# FPGA_34.net
KiCad netlist of a schematic drawn in Altium Designer
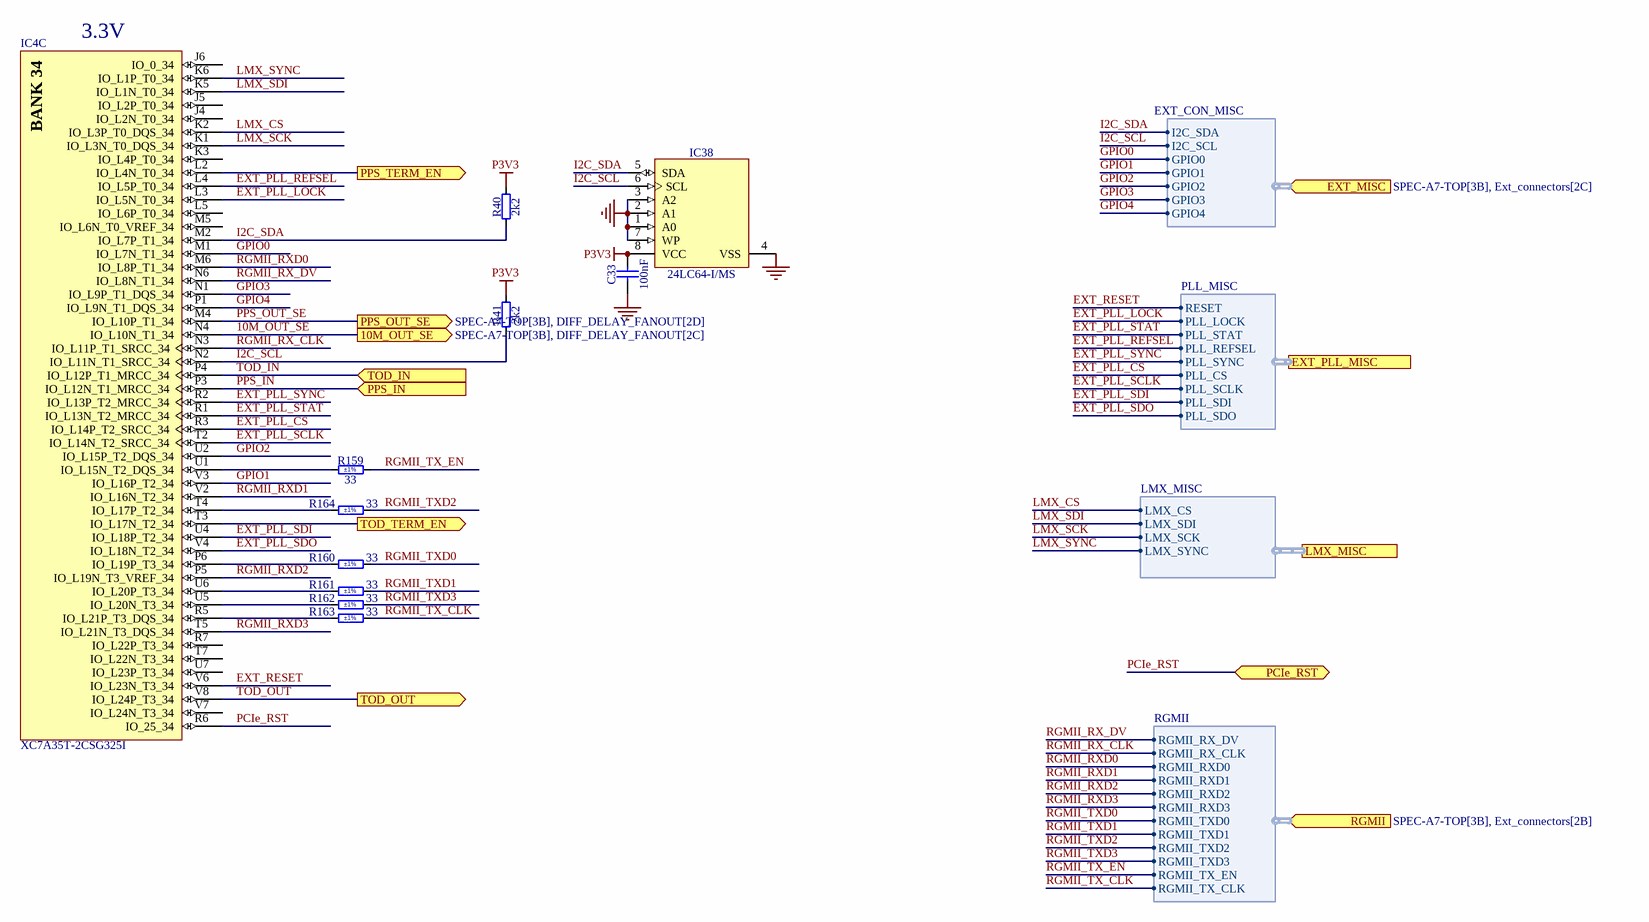
[diagram p0: FPGA_34.SchDoc]

(export (version "E")
  (design (tool "Eeschema 10.0.6"))
  (components
    (comp (ref "C33")
      (value "100nF")
      (footprint "CAPC0603X33N")
      (description "Non-polarised capacitor")
      (fields
        (field (name "PART NUMBER") "CC0201_100NF_6.3V_10%_X5R")
        (field (name "VOLTAGE") "6.3V")
        (field (name "AUTHOR") "CERN DEM JLC")
      )
      (libsource (lib "Capacitors") (part "Capacitor - non polarized"))
    )
    (comp (ref "IC4")
      (value "XC7A35T-2CSG325I")
      (footprint "CSG325")
      (description "Artix-7 FPGA, 150 User I/Os, 4 GTP, 324-Ball BGA, Speed Grade 2, Industrial Grade, Pb-Free")
      (fields (field (name "MANUFACTURER") "Xilinx"))
      (libsource (lib "Altium Content Vault") (part "XLNX-XC7A35T-CSG325"))
    )
    (comp (ref "IC38")
      (value "24LC64-I/MS")
      (footprint "SOP65P490X110-8N")
      (description "64K I2C Serial EEPROM")
      (fields (field (name "MANUFACTURER") "MICROCHIP TECHNOLOGY") (field (name "AUTHOR") "CERN DEM JLC"))
      (libsource (lib "ICs And Semiconductors") (part "24LC64-I/MS"))
    )
    (comp (ref "R40")
      (value "2k2")
      (footprint "RESC1005X40N")
      (description "Resistor - 1%")
      (fields
        (field (name "PART NUMBER") "R0402_2K2_1%_0.0625W_100PPM")
        (field (name "POWER") "0.0625W")
        (field (name "AUTHOR") "CERN DEM JLC")
      )
      (libsource (lib "Resistors") (part "Resistor - 1%"))
    )
    (comp (ref "R41")
      (value "2k2")
      (footprint "RESC1005X40N")
      (description "Resistor - 1%")
      (fields
        (field (name "PART NUMBER") "R0402_2K2_1%_0.0625W_100PPM")
        (field (name "POWER") "0.0625W")
        (field (name "AUTHOR") "CERN DEM JLC")
      )
      (libsource (lib "Resistors") (part "Resistor - 1%"))
    )
    (comp (ref "R159")
      (value "33")
      (footprint "RESC1005X40N")
      (description "Resistor - 1%")
      (fields
        (field (name "TOLERANCE") "±1%")
        (field (name "PART NUMBER") "R0402_33R_1%_0.0625W_100PPM")
        (field (name "POWER") "0.0625W")
        (field (name "AUTHOR") "CERN DEM JLC")
      )
      (libsource (lib "Resistors") (part "Resistor - 1%"))
    )
    (comp (ref "R160")
      (value "33")
      (footprint "RESC1005X40N")
      (description "Resistor - 1%")
      (fields
        (field (name "TOLERANCE") "±1%")
        (field (name "PART NUMBER") "R0402_33R_1%_0.0625W_100PPM")
        (field (name "POWER") "0.0625W")
        (field (name "AUTHOR") "CERN DEM JLC")
      )
      (libsource (lib "Resistors") (part "Resistor - 1%"))
    )
    (comp (ref "R161")
      (value "33")
      (footprint "RESC1005X40N")
      (description "Resistor - 1%")
      (fields
        (field (name "TOLERANCE") "±1%")
        (field (name "PART NUMBER") "R0402_33R_1%_0.0625W_100PPM")
        (field (name "POWER") "0.0625W")
        (field (name "AUTHOR") "CERN DEM JLC")
      )
      (libsource (lib "Resistors") (part "Resistor - 1%"))
    )
    (comp (ref "R162")
      (value "33")
      (footprint "RESC1005X40N")
      (description "Resistor - 1%")
      (fields
        (field (name "TOLERANCE") "±1%")
        (field (name "PART NUMBER") "R0402_33R_1%_0.0625W_100PPM")
        (field (name "POWER") "0.0625W")
        (field (name "AUTHOR") "CERN DEM JLC")
      )
      (libsource (lib "Resistors") (part "Resistor - 1%"))
    )
    (comp (ref "R163")
      (value "33")
      (footprint "RESC1005X40N")
      (description "Resistor - 1%")
      (fields
        (field (name "TOLERANCE") "±1%")
        (field (name "PART NUMBER") "R0402_33R_1%_0.0625W_100PPM")
        (field (name "POWER") "0.0625W")
        (field (name "AUTHOR") "CERN DEM JLC")
      )
      (libsource (lib "Resistors") (part "Resistor - 1%"))
    )
    (comp (ref "R164")
      (value "33")
      (footprint "RESC1005X40N")
      (description "Resistor - 1%")
      (fields
        (field (name "TOLERANCE") "±1%")
        (field (name "PART NUMBER") "R0402_33R_1%_0.0625W_100PPM")
        (field (name "POWER") "0.0625W")
        (field (name "AUTHOR") "CERN DEM JLC")
      )
      (libsource (lib "Resistors") (part "Resistor - 1%"))
    )
  )
  (nets
    (net (code "5") (name "/10M_OUT_SE") (class "Default")
      (node (ref "IC4") (pin "N4") (pinfunction "IO_L10N_T1_34_N4") (pintype "bidirectional"))
    )
    (net (code "6") (name "/EXT_PLL_CS") (class "Default")
      (node (ref "IC4") (pin "R3") (pinfunction "IO_L14P_T2_SRCC_34_R3") (pintype "bidirectional"))
    )
    (net (code "7") (name "/EXT_PLL_LOCK") (class "Default")
      (node (ref "IC4") (pin "L3") (pinfunction "IO_L5N_T0_34_L3") (pintype "bidirectional"))
    )
    (net (code "8") (name "/EXT_PLL_REFSEL") (class "Default")
      (node (ref "IC4") (pin "L4") (pinfunction "IO_L5P_T0_34_L4") (pintype "bidirectional"))
    )
    (net (code "9") (name "/EXT_PLL_SCLK") (class "Default")
      (node (ref "IC4") (pin "T2") (pinfunction "IO_L14N_T2_SRCC_34_T2") (pintype "bidirectional"))
    )
    (net (code "10") (name "/EXT_PLL_SDI") (class "Default")
      (node (ref "IC4") (pin "U4") (pinfunction "IO_L18P_T2_34_U4") (pintype "bidirectional"))
    )
    (net (code "11") (name "/EXT_PLL_SDO") (class "Default")
      (node (ref "IC4") (pin "V4") (pinfunction "IO_L18N_T2_34_V4") (pintype "bidirectional"))
    )
    (net (code "12") (name "/EXT_PLL_STAT") (class "Default")
      (node (ref "IC4") (pin "R1") (pinfunction "IO_L13N_T2_MRCC_34_R1") (pintype "bidirectional"))
    )
    (net (code "13") (name "/EXT_PLL_SYNC") (class "Default")
      (node (ref "IC4") (pin "R2") (pinfunction "IO_L13P_T2_MRCC_34_R2") (pintype "bidirectional"))
    )
    (net (code "14") (name "/EXT_RESET") (class "Default")
      (node (ref "IC4") (pin "V6") (pinfunction "IO_L23N_T3_34_V6") (pintype "bidirectional"))
    )
    (net (code "15") (name "/GPIO0") (class "Default")
      (node (ref "IC4") (pin "M1") (pinfunction "IO_L7N_T1_34_M1") (pintype "bidirectional"))
    )
    (net (code "16") (name "/GPIO1") (class "Default")
      (node (ref "IC4") (pin "V3") (pinfunction "IO_L16P_T2_34_V3") (pintype "bidirectional"))
    )
    (net (code "17") (name "/GPIO2") (class "Default")
      (node (ref "IC4") (pin "U2") (pinfunction "IO_L15P_T2_DQS_34_U2") (pintype "bidirectional"))
    )
    (net (code "18") (name "/GPIO3") (class "Default")
      (node (ref "IC4") (pin "N1") (pinfunction "IO_L9P_T1_DQS_34_N1") (pintype "bidirectional"))
    )
    (net (code "19") (name "/GPIO4") (class "Default")
      (node (ref "IC4") (pin "P1") (pinfunction "IO_L9N_T1_DQS_34_P1") (pintype "bidirectional"))
    )
    (net (code "20") (name "/I2C_SCL") (class "Default")
      (node (ref "IC38") (pin "6") (pinfunction "SCL_6") (pintype "input"))
      (node (ref "IC4") (pin "N2") (pinfunction "IO_L11N_T1_SRCC_34_N2") (pintype "bidirectional"))
      (node (ref "R41") (pin "1") (pinfunction "1_1") (pintype "passive"))
    )
    (net (code "21") (name "/I2C_SDA") (class "Default")
      (node (ref "IC38") (pin "5") (pinfunction "SDA_5") (pintype "bidirectional"))
      (node (ref "IC4") (pin "M2") (pinfunction "IO_L7P_T1_34_M2") (pintype "bidirectional"))
      (node (ref "R40") (pin "1") (pinfunction "1_1") (pintype "passive"))
    )
    (net (code "22") (name "/LMX_CS") (class "Default")
      (node (ref "IC4") (pin "K2") (pinfunction "IO_L3P_T0_DQS_34_K2") (pintype "bidirectional"))
    )
    (net (code "23") (name "/LMX_SCK") (class "Default")
      (node (ref "IC4") (pin "K1") (pinfunction "IO_L3N_T0_DQS_34_K1") (pintype "bidirectional"))
    )
    (net (code "24") (name "/LMX_SDI") (class "Default")
      (node (ref "IC4") (pin "K5") (pinfunction "IO_L1N_T0_34_K5") (pintype "bidirectional"))
    )
    (net (code "25") (name "/LMX_SYNC") (class "Default")
      (node (ref "IC4") (pin "K6") (pinfunction "IO_L1P_T0_34_K6") (pintype "bidirectional"))
    )
    (net (code "26") (name "/PCIe_RST") (class "Default")
      (node (ref "IC4") (pin "R6") (pinfunction "IO_25_34_R6") (pintype "bidirectional"))
    )
    (net (code "27") (name "/PPS_IN") (class "Default")
      (node (ref "IC4") (pin "P3") (pinfunction "IO_L12N_T1_MRCC_34_P3") (pintype "bidirectional"))
    )
    (net (code "28") (name "/PPS_OUT_SE") (class "Default")
      (node (ref "IC4") (pin "M4") (pinfunction "IO_L10P_T1_34_M4") (pintype "bidirectional"))
    )
    (net (code "29") (name "/PPS_TERM_EN") (class "Default")
      (node (ref "IC4") (pin "L2") (pinfunction "IO_L4N_T0_34_L2") (pintype "bidirectional"))
    )
    (net (code "30") (name "/RGMII_RXD0") (class "Default")
      (node (ref "IC4") (pin "M6") (pinfunction "IO_L8P_T1_34_M6") (pintype "bidirectional"))
    )
    (net (code "31") (name "/RGMII_RXD1") (class "Default")
      (node (ref "IC4") (pin "V2") (pinfunction "IO_L16N_T2_34_V2") (pintype "bidirectional"))
    )
    (net (code "32") (name "/RGMII_RXD2") (class "Default")
      (node (ref "IC4") (pin "P5") (pinfunction "IO_L19N_T3_VREF_34_P5") (pintype "bidirectional"))
    )
    (net (code "33") (name "/RGMII_RXD3") (class "Default")
      (node (ref "IC4") (pin "T5") (pinfunction "IO_L21N_T3_DQS_34_T5") (pintype "bidirectional"))
    )
    (net (code "34") (name "/RGMII_RX_CLK") (class "Default")
      (node (ref "IC4") (pin "N3") (pinfunction "IO_L11P_T1_SRCC_34_N3") (pintype "bidirectional"))
    )
    (net (code "35") (name "/RGMII_RX_DV") (class "Default")
      (node (ref "IC4") (pin "N6") (pinfunction "IO_L8N_T1_34_N6") (pintype "bidirectional"))
    )
    (net (code "36") (name "/RGMII_TXD0") (class "Default")
      (node (ref "R160") (pin "2") (pinfunction "2_2") (pintype "passive"))
    )
    (net (code "37") (name "/RGMII_TXD1") (class "Default")
      (node (ref "R161") (pin "2") (pinfunction "2_2") (pintype "passive"))
    )
    (net (code "38") (name "/RGMII_TXD2") (class "Default")
      (node (ref "R164") (pin "2") (pinfunction "2_2") (pintype "passive"))
    )
    (net (code "39") (name "/RGMII_TXD3") (class "Default")
      (node (ref "R162") (pin "2") (pinfunction "2_2") (pintype "passive"))
    )
    (net (code "40") (name "/RGMII_TX_CLK") (class "Default")
      (node (ref "R163") (pin "2") (pinfunction "2_2") (pintype "passive"))
    )
    (net (code "41") (name "/RGMII_TX_EN") (class "Default")
      (node (ref "R159") (pin "2") (pinfunction "2_2") (pintype "passive"))
    )
    (net (code "42") (name "/TOD_IN") (class "Default")
      (node (ref "IC4") (pin "P4") (pinfunction "IO_L12P_T1_MRCC_34_P4") (pintype "bidirectional"))
    )
    (net (code "43") (name "/TOD_OUT") (class "Default")
      (node (ref "IC4") (pin "V8") (pinfunction "IO_L24P_T3_34_V8") (pintype "bidirectional"))
    )
    (net (code "44") (name "/TOD_TERM_EN") (class "Default")
      (node (ref "IC4") (pin "T3") (pinfunction "IO_L17N_T2_34_T3") (pintype "bidirectional"))
    )
    (net (code "49") (name "GND") (class "Default")
      (node (ref "C33") (pin "1") (pinfunction "1_1") (pintype "passive"))
      (node (ref "IC38") (pin "1") (pinfunction "A0_1") (pintype "input"))
      (node (ref "IC38") (pin "2") (pinfunction "A1_2") (pintype "input"))
      (node (ref "IC38") (pin "3") (pinfunction "A2_3") (pintype "input"))
      (node (ref "IC38") (pin "4") (pinfunction "VSS_4") (pintype "power_in"))
      (node (ref "IC38") (pin "7") (pinfunction "WP_7") (pintype "input"))
    )
    (net (code "50") (name "Net-(IC4C-IO_L15N_T2_DQS_34)") (class "Default")
      (node (ref "IC4") (pin "U1") (pinfunction "IO_L15N_T2_DQS_34_U1") (pintype "bidirectional"))
      (node (ref "R159") (pin "1") (pinfunction "1_1") (pintype "passive"))
    )
    (net (code "51") (name "Net-(IC4C-IO_L17P_T2_34)") (class "Default")
      (node (ref "IC4") (pin "T4") (pinfunction "IO_L17P_T2_34_T4") (pintype "bidirectional"))
      (node (ref "R164") (pin "1") (pinfunction "1_1") (pintype "passive"))
    )
    (net (code "52") (name "Net-(IC4C-IO_L19P_T3_34)") (class "Default")
      (node (ref "IC4") (pin "P6") (pinfunction "IO_L19P_T3_34_P6") (pintype "bidirectional"))
      (node (ref "R160") (pin "1") (pinfunction "1_1") (pintype "passive"))
    )
    (net (code "53") (name "Net-(IC4C-IO_L20N_T3_34)") (class "Default")
      (node (ref "IC4") (pin "U5") (pinfunction "IO_L20N_T3_34_U5") (pintype "bidirectional"))
      (node (ref "R162") (pin "1") (pinfunction "1_1") (pintype "passive"))
    )
    (net (code "54") (name "Net-(IC4C-IO_L20P_T3_34)") (class "Default")
      (node (ref "IC4") (pin "U6") (pinfunction "IO_L20P_T3_34_U6") (pintype "bidirectional"))
      (node (ref "R161") (pin "1") (pinfunction "1_1") (pintype "passive"))
    )
    (net (code "55") (name "Net-(IC4C-IO_L21P_T3_DQS_34)") (class "Default")
      (node (ref "IC4") (pin "R5") (pinfunction "IO_L21P_T3_DQS_34_R5") (pintype "bidirectional"))
      (node (ref "R163") (pin "1") (pinfunction "1_1") (pintype "passive"))
    )
    (net (code "56") (name "P3V3") (class "Default")
      (node (ref "C33") (pin "2") (pinfunction "2_2") (pintype "passive"))
      (node (ref "IC38") (pin "8") (pinfunction "VCC_8") (pintype "power_in"))
      (node (ref "R40") (pin "2") (pinfunction "2_2") (pintype "passive"))
      (node (ref "R41") (pin "2") (pinfunction "2_2") (pintype "passive"))
    )
    (net (code "57") (name "unconnected-(IC4C-IO_0_34-PadJ6)") (class "Default")
      (node (ref "IC4") (pin "J6") (pinfunction "IO_0_34_J6") (pintype "bidirectional"))
    )
    (net (code "58") (name "unconnected-(IC4C-IO_L2N_T0_34-PadJ4)") (class "Default")
      (node (ref "IC4") (pin "J4") (pinfunction "IO_L2N_T0_34_J4") (pintype "bidirectional"))
    )
    (net (code "59") (name "unconnected-(IC4C-IO_L2P_T0_34-PadJ5)") (class "Default")
      (node (ref "IC4") (pin "J5") (pinfunction "IO_L2P_T0_34_J5") (pintype "bidirectional"))
    )
    (net (code "60") (name "unconnected-(IC4C-IO_L4P_T0_34-PadK3)") (class "Default")
      (node (ref "IC4") (pin "K3") (pinfunction "IO_L4P_T0_34_K3") (pintype "bidirectional"))
    )
    (net (code "61") (name "unconnected-(IC4C-IO_L6N_T0_VREF_34-PadM5)") (class "Default")
      (node (ref "IC4") (pin "M5") (pinfunction "IO_L6N_T0_VREF_34_M5") (pintype "bidirectional"))
    )
    (net (code "62") (name "unconnected-(IC4C-IO_L6P_T0_34-PadL5)") (class "Default")
      (node (ref "IC4") (pin "L5") (pinfunction "IO_L6P_T0_34_L5") (pintype "bidirectional"))
    )
    (net (code "63") (name "unconnected-(IC4C-IO_L22N_T3_34-PadT7)") (class "Default")
      (node (ref "IC4") (pin "T7") (pinfunction "IO_L22N_T3_34_T7") (pintype "bidirectional"))
    )
    (net (code "64") (name "unconnected-(IC4C-IO_L22P_T3_34-PadR7)") (class "Default")
      (node (ref "IC4") (pin "R7") (pinfunction "IO_L22P_T3_34_R7") (pintype "bidirectional"))
    )
    (net (code "65") (name "unconnected-(IC4C-IO_L23P_T3_34-PadU7)") (class "Default")
      (node (ref "IC4") (pin "U7") (pinfunction "IO_L23P_T3_34_U7") (pintype "bidirectional"))
    )
    (net (code "66") (name "unconnected-(IC4C-IO_L24N_T3_34-PadV7)") (class "Default")
      (node (ref "IC4") (pin "V7") (pinfunction "IO_L24N_T3_34_V7") (pintype "bidirectional"))
    )
  )
)
